# AudioControllerSchematic_Photoresistor.net
KiCad netlist of a schematic drawn in EAGLE
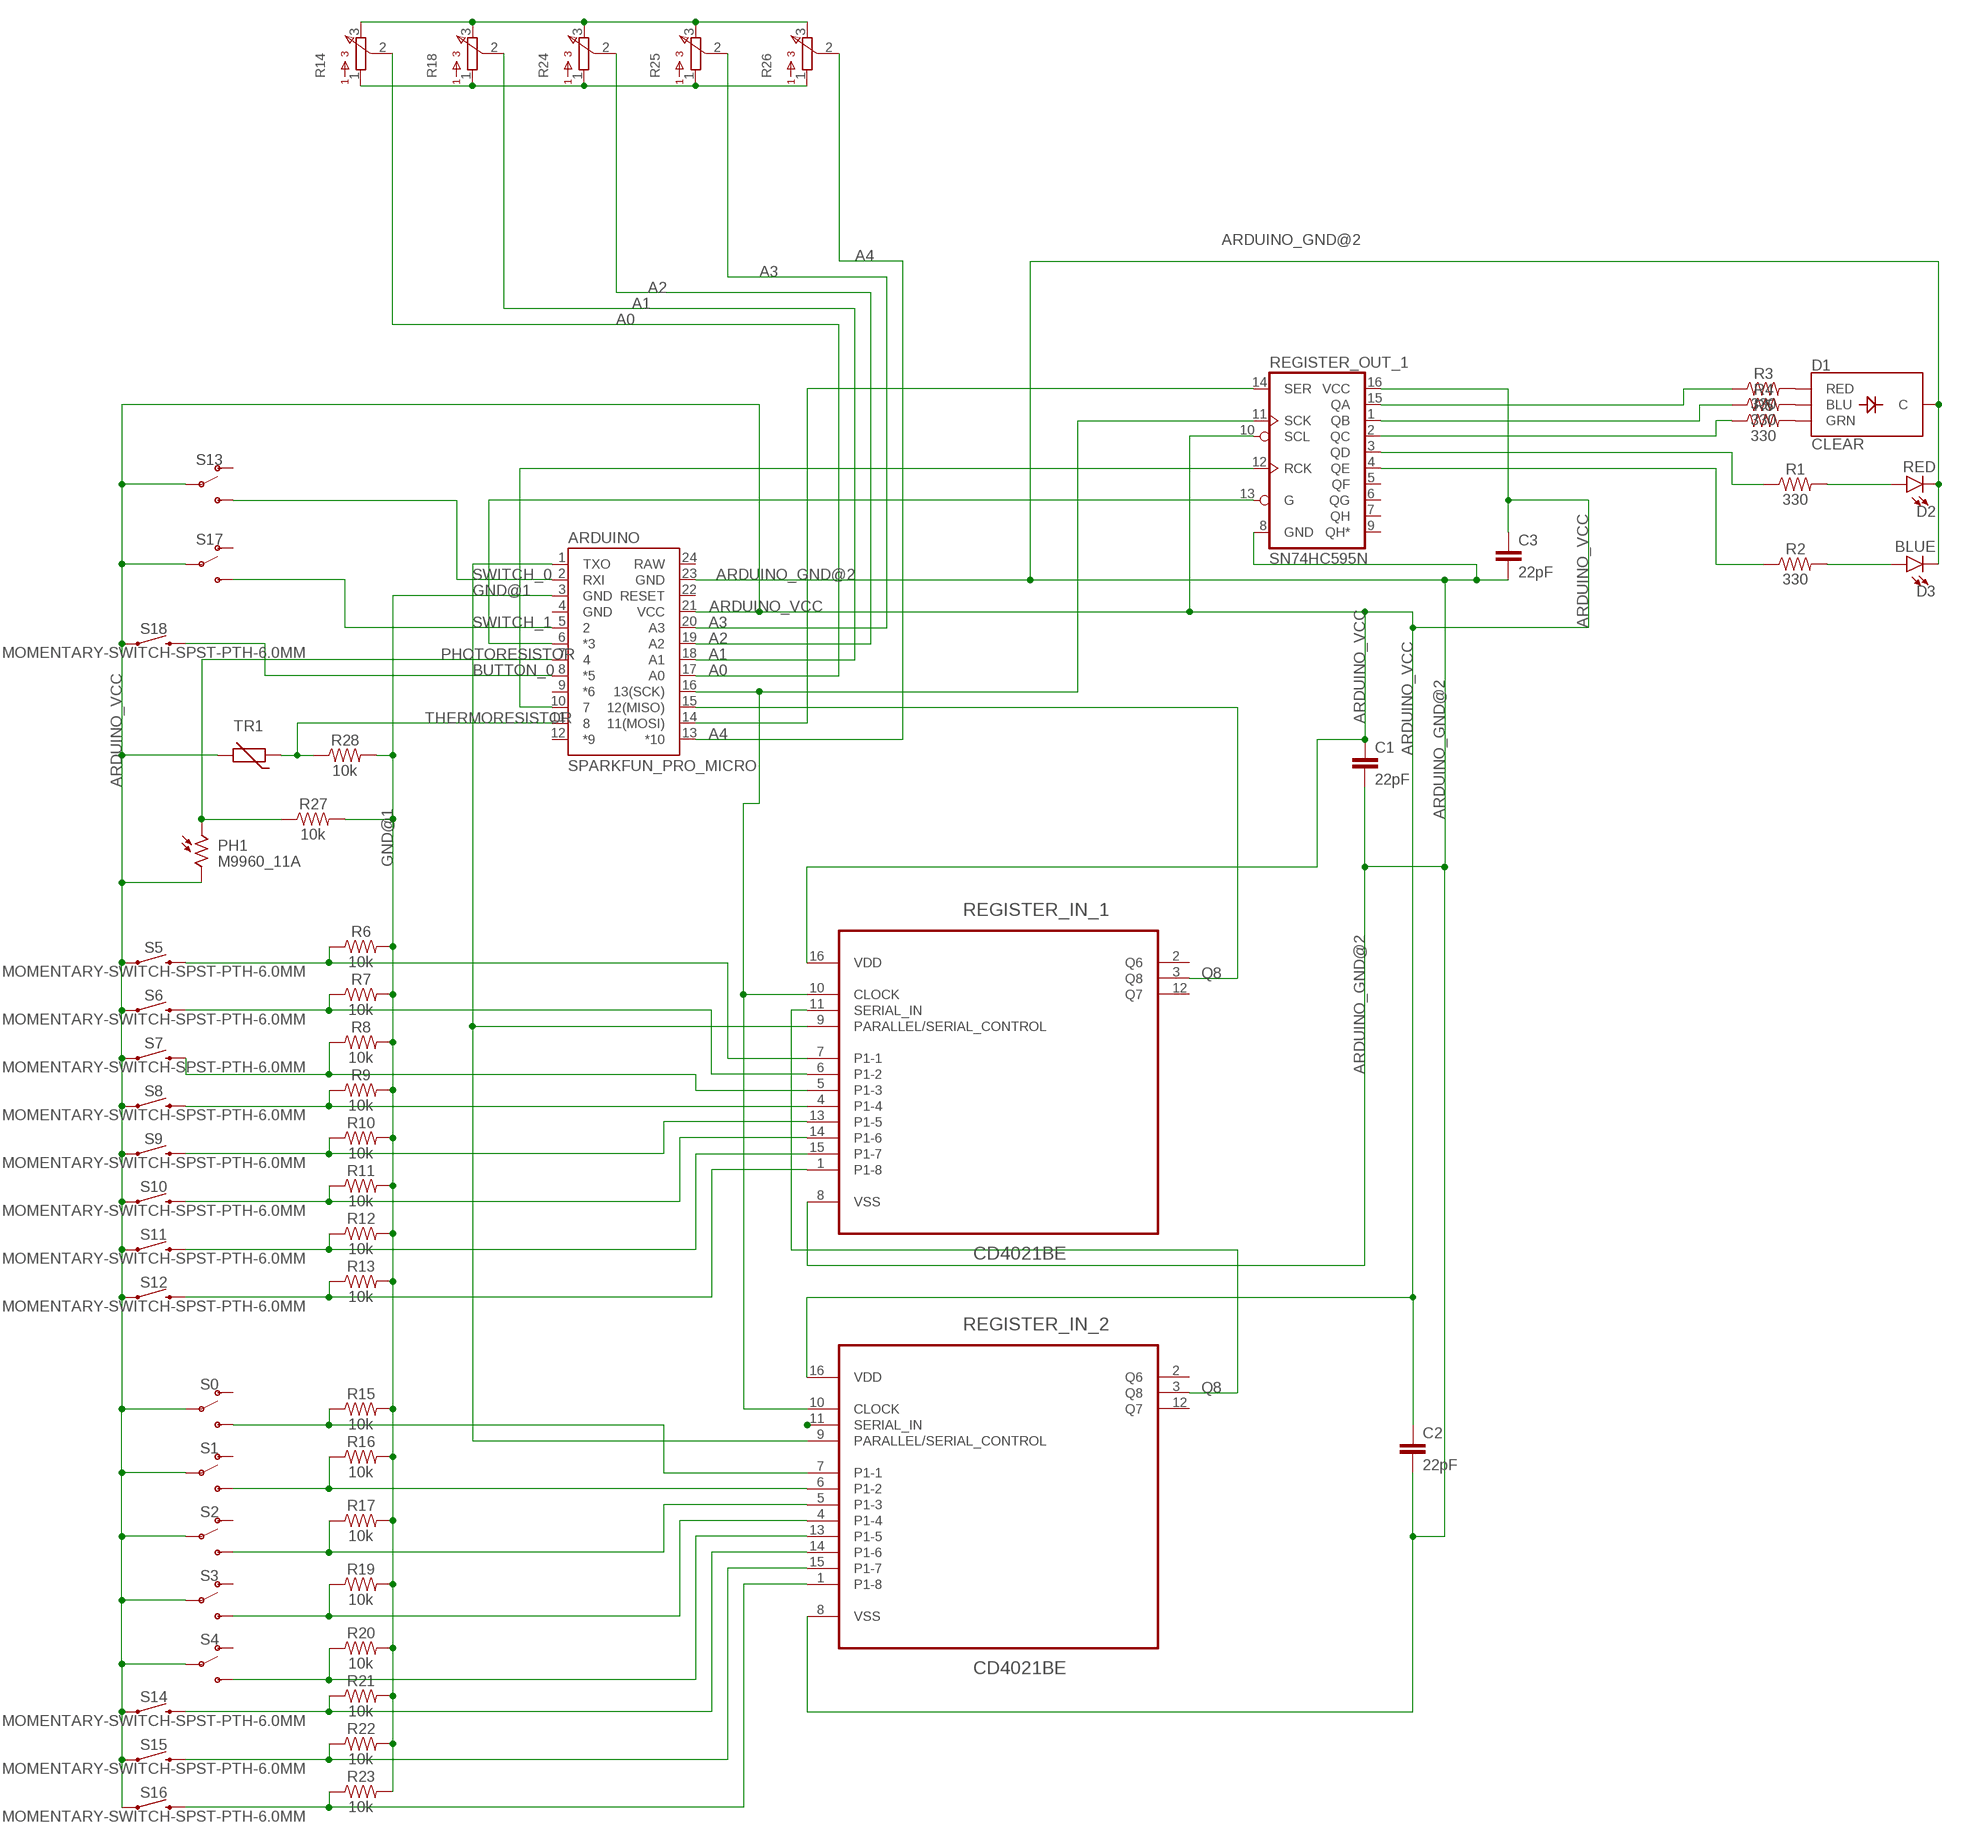
[diagram p0: schematic, sheet 1]

(export (version "E")
  (design (tool "Eeschema 10.0.6"))
  (components
    (comp (ref "ARDUINO")
      (value "SPARKFUN_PRO_MICRO")
      (footprint "eagle-import:SPARKFUN_PRO_MICRO")
      (libsource (lib "eagle-import") (part "SPARKFUN_PRO_MICRO"))
    )
    (comp (ref "C1")
      (value "22pF")
      (footprint "eagle-import:0603")
      (libsource (lib "eagle-import") (part "22PF-0603-50V-5%"))
    )
    (comp (ref "C2")
      (value "22pF")
      (footprint "eagle-import:0603")
      (libsource (lib "eagle-import") (part "22PF-0603-50V-5%"))
    )
    (comp (ref "C3")
      (value "22pF")
      (footprint "eagle-import:0603")
      (libsource (lib "eagle-import") (part "22PF-0603-50V-5%"))
    )
    (comp (ref "D1")
      (value "CLEAR")
      (footprint "eagle-import:LED-RGB-THRU")
      (libsource (lib "eagle-import") (part "LED-RGB-CCCLEAR"))
    )
    (comp (ref "D2")
      (value "RED")
      (footprint "eagle-import:LED-0603")
      (libsource (lib "eagle-import") (part "LED-RED0603"))
    )
    (comp (ref "D3")
      (value "BLUE")
      (footprint "eagle-import:LED-0603")
      (libsource (lib "eagle-import") (part "LED-BLUE0603"))
    )
    (comp (ref "PH1")
      (value "M9960_11A")
      (footprint "eagle-import:M9960")
      (libsource (lib "eagle-import") (part "M9960_11A"))
    )
    (comp (ref "R1")
      (value "330")
      (footprint "eagle-import:0603")
      (libsource (lib "eagle-import") (part "330OHM-0603-1/10W-1%"))
    )
    (comp (ref "R2")
      (value "330")
      (footprint "eagle-import:0603")
      (libsource (lib "eagle-import") (part "330OHM-0603-1/10W-1%"))
    )
    (comp (ref "R3")
      (value "330")
      (footprint "eagle-import:0603")
      (libsource (lib "eagle-import") (part "330OHM-0603-1/10W-1%"))
    )
    (comp (ref "R4")
      (value "330")
      (footprint "eagle-import:0603")
      (libsource (lib "eagle-import") (part "330OHM-0603-1/10W-1%"))
    )
    (comp (ref "R5")
      (value "330")
      (footprint "eagle-import:0603")
      (libsource (lib "eagle-import") (part "330OHM-0603-1/10W-1%"))
    )
    (comp (ref "R6")
      (value "10k")
      (footprint "eagle-import:0603")
      (libsource (lib "eagle-import") (part "10KOHM-0603-1/10W-1%"))
    )
    (comp (ref "R7")
      (value "10k")
      (footprint "eagle-import:0603")
      (libsource (lib "eagle-import") (part "10KOHM-0603-1/10W-1%"))
    )
    (comp (ref "R8")
      (value "10k")
      (footprint "eagle-import:0603")
      (libsource (lib "eagle-import") (part "10KOHM-0603-1/10W-1%"))
    )
    (comp (ref "R9")
      (value "10k")
      (footprint "eagle-import:0603")
      (libsource (lib "eagle-import") (part "10KOHM-0603-1/10W-1%"))
    )
    (comp (ref "R10")
      (value "10k")
      (footprint "eagle-import:0603")
      (libsource (lib "eagle-import") (part "10KOHM-0603-1/10W-1%"))
    )
    (comp (ref "R11")
      (value "10k")
      (footprint "eagle-import:0603")
      (libsource (lib "eagle-import") (part "10KOHM-0603-1/10W-1%"))
    )
    (comp (ref "R12")
      (value "10k")
      (footprint "eagle-import:0603")
      (libsource (lib "eagle-import") (part "10KOHM-0603-1/10W-1%"))
    )
    (comp (ref "R13")
      (value "10k")
      (footprint "eagle-import:0603")
      (libsource (lib "eagle-import") (part "10KOHM-0603-1/10W-1%"))
    )
    (comp (ref "R14") (value "91") (footprint "eagle-import:91") (libsource (lib "eagle-import") (part "91")))
    (comp (ref "R15")
      (value "10k")
      (footprint "eagle-import:0603")
      (libsource (lib "eagle-import") (part "10KOHM-0603-1/10W-1%"))
    )
    (comp (ref "R16")
      (value "10k")
      (footprint "eagle-import:0603")
      (libsource (lib "eagle-import") (part "10KOHM-0603-1/10W-1%"))
    )
    (comp (ref "R17")
      (value "10k")
      (footprint "eagle-import:0603")
      (libsource (lib "eagle-import") (part "10KOHM-0603-1/10W-1%"))
    )
    (comp (ref "R18") (value "91") (footprint "eagle-import:91") (libsource (lib "eagle-import") (part "91")))
    (comp (ref "R19")
      (value "10k")
      (footprint "eagle-import:0603")
      (libsource (lib "eagle-import") (part "10KOHM-0603-1/10W-1%"))
    )
    (comp (ref "R20")
      (value "10k")
      (footprint "eagle-import:0603")
      (libsource (lib "eagle-import") (part "10KOHM-0603-1/10W-1%"))
    )
    (comp (ref "R21")
      (value "10k")
      (footprint "eagle-import:0603")
      (libsource (lib "eagle-import") (part "10KOHM-0603-1/10W-1%"))
    )
    (comp (ref "R22")
      (value "10k")
      (footprint "eagle-import:0603")
      (libsource (lib "eagle-import") (part "10KOHM-0603-1/10W-1%"))
    )
    (comp (ref "R23")
      (value "10k")
      (footprint "eagle-import:0603")
      (libsource (lib "eagle-import") (part "10KOHM-0603-1/10W-1%"))
    )
    (comp (ref "R24") (value "91") (footprint "eagle-import:91") (libsource (lib "eagle-import") (part "91")))
    (comp (ref "R25") (value "91") (footprint "eagle-import:91") (libsource (lib "eagle-import") (part "91")))
    (comp (ref "R26") (value "91") (footprint "eagle-import:91") (libsource (lib "eagle-import") (part "91")))
    (comp (ref "R27")
      (value "10k")
      (footprint "eagle-import:0603")
      (libsource (lib "eagle-import") (part "10KOHM-0603-1/10W-1%"))
    )
    (comp (ref "R28")
      (value "10k")
      (footprint "eagle-import:0603")
      (libsource (lib "eagle-import") (part "10KOHM-0603-1/10W-1%"))
    )
    (comp (ref "REGISTER_IN_1")
      (value "CD4021BE")
      (footprint "eagle-import:DIP254P762X508-16")
      (fields (field (name "MF") "Texas"))
      (libsource (lib "eagle-import") (part "CD4021BE"))
    )
    (comp (ref "REGISTER_IN_2")
      (value "CD4021BE")
      (footprint "eagle-import:DIP254P762X508-16")
      (fields (field (name "MF") "Texas"))
      (libsource (lib "eagle-import") (part "CD4021BE"))
    )
    (comp (ref "REGISTER_OUT_1")
      (value "SN74HC595N")
      (footprint "eagle-import:DIP16")
      (libsource (lib "eagle-import") (part "74595NHC"))
    )
    (comp (ref "S0")
      (value "SWITCH-SPDT-PTH-11.6X4.0MM")
      (footprint "eagle-import:SWITCH_SPDT_PTH_11.6X4.0MM")
      (libsource (lib "eagle-import") (part "SWITCH-SPDT-PTH-11.6X4.0MM"))
    )
    (comp (ref "S1")
      (value "SWITCH-SPDT-PTH-11.6X4.0MM")
      (footprint "eagle-import:SWITCH_SPDT_PTH_11.6X4.0MM")
      (libsource (lib "eagle-import") (part "SWITCH-SPDT-PTH-11.6X4.0MM"))
    )
    (comp (ref "S2")
      (value "SWITCH-SPDT-PTH-11.6X4.0MM")
      (footprint "eagle-import:SWITCH_SPDT_PTH_11.6X4.0MM")
      (libsource (lib "eagle-import") (part "SWITCH-SPDT-PTH-11.6X4.0MM"))
    )
    (comp (ref "S3")
      (value "SWITCH-SPDT-PTH-11.6X4.0MM")
      (footprint "eagle-import:SWITCH_SPDT_PTH_11.6X4.0MM")
      (libsource (lib "eagle-import") (part "SWITCH-SPDT-PTH-11.6X4.0MM"))
    )
    (comp (ref "S4")
      (value "SWITCH-SPDT-PTH-11.6X4.0MM")
      (footprint "eagle-import:SWITCH_SPDT_PTH_11.6X4.0MM")
      (libsource (lib "eagle-import") (part "SWITCH-SPDT-PTH-11.6X4.0MM"))
    )
    (comp (ref "S5")
      (value "MOMENTARY-SWITCH-SPST-PTH-6.0MM")
      (footprint "eagle-import:TACTILE_SWITCH_PTH_6.0MM")
      (libsource (lib "eagle-import") (part "MOMENTARY-SWITCH-SPST-PTH-6.0MM"))
    )
    (comp (ref "S6")
      (value "MOMENTARY-SWITCH-SPST-PTH-6.0MM")
      (footprint "eagle-import:TACTILE_SWITCH_PTH_6.0MM")
      (libsource (lib "eagle-import") (part "MOMENTARY-SWITCH-SPST-PTH-6.0MM"))
    )
    (comp (ref "S7")
      (value "MOMENTARY-SWITCH-SPST-PTH-6.0MM")
      (footprint "eagle-import:TACTILE_SWITCH_PTH_6.0MM")
      (libsource (lib "eagle-import") (part "MOMENTARY-SWITCH-SPST-PTH-6.0MM"))
    )
    (comp (ref "S8")
      (value "MOMENTARY-SWITCH-SPST-PTH-6.0MM")
      (footprint "eagle-import:TACTILE_SWITCH_PTH_6.0MM")
      (libsource (lib "eagle-import") (part "MOMENTARY-SWITCH-SPST-PTH-6.0MM"))
    )
    (comp (ref "S9")
      (value "MOMENTARY-SWITCH-SPST-PTH-6.0MM")
      (footprint "eagle-import:TACTILE_SWITCH_PTH_6.0MM")
      (libsource (lib "eagle-import") (part "MOMENTARY-SWITCH-SPST-PTH-6.0MM"))
    )
    (comp (ref "S10")
      (value "MOMENTARY-SWITCH-SPST-PTH-6.0MM")
      (footprint "eagle-import:TACTILE_SWITCH_PTH_6.0MM")
      (libsource (lib "eagle-import") (part "MOMENTARY-SWITCH-SPST-PTH-6.0MM"))
    )
    (comp (ref "S11")
      (value "MOMENTARY-SWITCH-SPST-PTH-6.0MM")
      (footprint "eagle-import:TACTILE_SWITCH_PTH_6.0MM")
      (libsource (lib "eagle-import") (part "MOMENTARY-SWITCH-SPST-PTH-6.0MM"))
    )
    (comp (ref "S12")
      (value "MOMENTARY-SWITCH-SPST-PTH-6.0MM")
      (footprint "eagle-import:TACTILE_SWITCH_PTH_6.0MM")
      (libsource (lib "eagle-import") (part "MOMENTARY-SWITCH-SPST-PTH-6.0MM"))
    )
    (comp (ref "S13")
      (value "SWITCH-SPDT-PTH-11.6X4.0MM")
      (footprint "eagle-import:SWITCH_SPDT_PTH_11.6X4.0MM")
      (libsource (lib "eagle-import") (part "SWITCH-SPDT-PTH-11.6X4.0MM"))
    )
    (comp (ref "S14")
      (value "MOMENTARY-SWITCH-SPST-PTH-6.0MM")
      (footprint "eagle-import:TACTILE_SWITCH_PTH_6.0MM")
      (libsource (lib "eagle-import") (part "MOMENTARY-SWITCH-SPST-PTH-6.0MM"))
    )
    (comp (ref "S15")
      (value "MOMENTARY-SWITCH-SPST-PTH-6.0MM")
      (footprint "eagle-import:TACTILE_SWITCH_PTH_6.0MM")
      (libsource (lib "eagle-import") (part "MOMENTARY-SWITCH-SPST-PTH-6.0MM"))
    )
    (comp (ref "S16")
      (value "MOMENTARY-SWITCH-SPST-PTH-6.0MM")
      (footprint "eagle-import:TACTILE_SWITCH_PTH_6.0MM")
      (libsource (lib "eagle-import") (part "MOMENTARY-SWITCH-SPST-PTH-6.0MM"))
    )
    (comp (ref "S17")
      (value "SWITCH-SPDT-PTH-11.6X4.0MM")
      (footprint "eagle-import:SWITCH_SPDT_PTH_11.6X4.0MM")
      (libsource (lib "eagle-import") (part "SWITCH-SPDT-PTH-11.6X4.0MM"))
    )
    (comp (ref "S18")
      (value "MOMENTARY-SWITCH-SPST-PTH-6.0MM")
      (footprint "eagle-import:TACTILE_SWITCH_PTH_6.0MM")
      (libsource (lib "eagle-import") (part "MOMENTARY-SWITCH-SPST-PTH-6.0MM"))
    )
    (comp (ref "TR1")
      (value "THERMISTOR_R-2,5")
      (footprint "eagle-import:RS-2,5")
      (libsource (lib "eagle-import") (part "THERMISTOR_R-2,5"))
    )
  )
  (nets
    (net (code "1") (name "/A0") (class "Default")
      (node (ref "ARDUINO") (pin "17") (pinfunction "A0_17") (pintype "bidirectional"))
      (node (ref "R14") (pin "2") (pinfunction "2_2") (pintype "passive"))
    )
    (net (code "2") (name "/A1") (class "Default")
      (node (ref "ARDUINO") (pin "18") (pinfunction "A1_18") (pintype "bidirectional"))
      (node (ref "R18") (pin "2") (pinfunction "2_2") (pintype "passive"))
    )
    (net (code "3") (name "/A2") (class "Default")
      (node (ref "ARDUINO") (pin "19") (pinfunction "A2_19") (pintype "bidirectional"))
      (node (ref "R24") (pin "2") (pinfunction "2_2") (pintype "passive"))
    )
    (net (code "4") (name "/A3") (class "Default")
      (node (ref "ARDUINO") (pin "20") (pinfunction "A3_20") (pintype "bidirectional"))
      (node (ref "R25") (pin "2") (pinfunction "2_2") (pintype "passive"))
    )
    (net (code "5") (name "/A4") (class "Default")
      (node (ref "ARDUINO") (pin "13") (pinfunction "*10_13") (pintype "bidirectional"))
      (node (ref "R26") (pin "2") (pinfunction "2_2") (pintype "passive"))
    )
    (net (code "6") (name "/ARDUINO_GND@2") (class "Default")
      (node (ref "ARDUINO") (pin "23") (pinfunction "GND_23") (pintype "power_in"))
      (node (ref "C1") (pin "2") (pinfunction "2_2") (pintype "passive"))
      (node (ref "C2") (pin "2") (pinfunction "2_2") (pintype "passive"))
      (node (ref "C3") (pin "2") (pinfunction "2_2") (pintype "passive"))
      (node (ref "D1") (pin "2") (pinfunction "C_2") (pintype "bidirectional"))
      (node (ref "D2") (pin "C") (pinfunction "C_C") (pintype "passive"))
      (node (ref "D3") (pin "C") (pinfunction "C_C") (pintype "passive"))
      (node (ref "REGISTER_IN_1") (pin "8") (pinfunction "VSS_8") (pintype "passive"))
      (node (ref "REGISTER_IN_2") (pin "8") (pinfunction "VSS_8") (pintype "passive"))
      (node (ref "REGISTER_OUT_1") (pin "8") (pinfunction "GND_8") (pintype "power_in"))
    )
    (net (code "7") (name "/ARDUINO_VCC") (class "Default")
      (node (ref "ARDUINO") (pin "21") (pinfunction "VCC_21") (pintype "power_in"))
      (node (ref "C1") (pin "1") (pinfunction "1_1") (pintype "passive"))
      (node (ref "C2") (pin "1") (pinfunction "1_1") (pintype "passive"))
      (node (ref "C3") (pin "1") (pinfunction "1_1") (pintype "passive"))
      (node (ref "PH1") (pin "2") (pinfunction "2_2") (pintype "passive"))
      (node (ref "REGISTER_IN_1") (pin "16") (pinfunction "VDD_16") (pintype "power_in"))
      (node (ref "REGISTER_IN_2") (pin "16") (pinfunction "VDD_16") (pintype "power_in"))
      (node (ref "REGISTER_OUT_1") (pin "10") (pinfunction "SCL_10") (pintype "input"))
      (node (ref "REGISTER_OUT_1") (pin "16") (pinfunction "VCC_16") (pintype "power_in"))
      (node (ref "S0") (pin "2") (pinfunction "P_2") (pintype "passive"))
      (node (ref "S1") (pin "2") (pinfunction "P_2") (pintype "passive"))
      (node (ref "S10") (pin "1") (pinfunction "1_1") (pintype "passive"))
      (node (ref "S11") (pin "1") (pinfunction "1_1") (pintype "passive"))
      (node (ref "S12") (pin "1") (pinfunction "1_1") (pintype "passive"))
      (node (ref "S13") (pin "2") (pinfunction "P_2") (pintype "passive"))
      (node (ref "S14") (pin "1") (pinfunction "1_1") (pintype "passive"))
      (node (ref "S15") (pin "1") (pinfunction "1_1") (pintype "passive"))
      (node (ref "S16") (pin "1") (pinfunction "1_1") (pintype "passive"))
      (node (ref "S17") (pin "2") (pinfunction "P_2") (pintype "passive"))
      (node (ref "S18") (pin "1") (pinfunction "1_1") (pintype "passive"))
      (node (ref "S2") (pin "2") (pinfunction "P_2") (pintype "passive"))
      (node (ref "S3") (pin "2") (pinfunction "P_2") (pintype "passive"))
      (node (ref "S4") (pin "2") (pinfunction "P_2") (pintype "passive"))
      (node (ref "S5") (pin "1") (pinfunction "1_1") (pintype "passive"))
      (node (ref "S6") (pin "1") (pinfunction "1_1") (pintype "passive"))
      (node (ref "S7") (pin "1") (pinfunction "1_1") (pintype "passive"))
      (node (ref "S8") (pin "1") (pinfunction "1_1") (pintype "passive"))
      (node (ref "S9") (pin "1") (pinfunction "1_1") (pintype "passive"))
      (node (ref "TR1") (pin "2") (pinfunction "2_2") (pintype "passive"))
    )
    (net (code "8") (name "/BUTTON_0") (class "Default")
      (node (ref "ARDUINO") (pin "8") (pinfunction "*5_8") (pintype "bidirectional"))
      (node (ref "S18") (pin "3") (pinfunction "2_3") (pintype "passive"))
    )
    (net (code "9") (name "/GND") (class "Default")
      (node (ref "ARDUINO") (pin "4") (pinfunction "GND_4") (pintype "power_in"))
    )
    (net (code "10") (name "/GND@1") (class "Default")
      (node (ref "ARDUINO") (pin "3") (pinfunction "GND_3") (pintype "power_in"))
      (node (ref "R10") (pin "2") (pinfunction "2_2") (pintype "passive"))
      (node (ref "R11") (pin "2") (pinfunction "2_2") (pintype "passive"))
      (node (ref "R12") (pin "2") (pinfunction "2_2") (pintype "passive"))
      (node (ref "R13") (pin "2") (pinfunction "2_2") (pintype "passive"))
      (node (ref "R15") (pin "2") (pinfunction "2_2") (pintype "passive"))
      (node (ref "R16") (pin "2") (pinfunction "2_2") (pintype "passive"))
      (node (ref "R17") (pin "2") (pinfunction "2_2") (pintype "passive"))
      (node (ref "R19") (pin "2") (pinfunction "2_2") (pintype "passive"))
      (node (ref "R20") (pin "2") (pinfunction "2_2") (pintype "passive"))
      (node (ref "R21") (pin "2") (pinfunction "2_2") (pintype "passive"))
      (node (ref "R22") (pin "2") (pinfunction "2_2") (pintype "passive"))
      (node (ref "R23") (pin "2") (pinfunction "2_2") (pintype "passive"))
      (node (ref "R27") (pin "2") (pinfunction "2_2") (pintype "passive"))
      (node (ref "R28") (pin "2") (pinfunction "2_2") (pintype "passive"))
      (node (ref "R6") (pin "2") (pinfunction "2_2") (pintype "passive"))
      (node (ref "R7") (pin "2") (pinfunction "2_2") (pintype "passive"))
      (node (ref "R8") (pin "2") (pinfunction "2_2") (pintype "passive"))
      (node (ref "R9") (pin "2") (pinfunction "2_2") (pintype "passive"))
    )
    (net (code "11") (name "/PHOTORESISTOR") (class "Default")
      (node (ref "ARDUINO") (pin "7") (pinfunction "4_7") (pintype "bidirectional"))
      (node (ref "PH1") (pin "1") (pinfunction "1_1") (pintype "passive"))
      (node (ref "R27") (pin "1") (pinfunction "1_1") (pintype "passive"))
    )
    (net (code "12") (name "/Q8") (class "Default")
      (node (ref "ARDUINO") (pin "15") (pinfunction "12(MISO)_15") (pintype "bidirectional"))
      (node (ref "REGISTER_IN_1") (pin "11") (pinfunction "SERIAL_IN_11") (pintype "input"))
      (node (ref "REGISTER_IN_1") (pin "3") (pinfunction "Q8_3") (pintype "output"))
      (node (ref "REGISTER_IN_2") (pin "3") (pinfunction "Q8_3") (pintype "output"))
    )
    (net (code "13") (name "/RAW") (class "Default")
      (node (ref "ARDUINO") (pin "24") (pinfunction "RAW_24") (pintype "power_in"))
    )
    (net (code "14") (name "/SWITCH_0") (class "Default")
      (node (ref "ARDUINO") (pin "2") (pinfunction "RXI_2") (pintype "bidirectional"))
      (node (ref "S13") (pin "3") (pinfunction "S_3") (pintype "passive"))
    )
    (net (code "15") (name "/SWITCH_1") (class "Default")
      (node (ref "ARDUINO") (pin "5") (pinfunction "2_5") (pintype "bidirectional"))
      (node (ref "S17") (pin "3") (pinfunction "S_3") (pintype "passive"))
    )
    (net (code "16") (name "/THERMORESISTOR") (class "Default")
      (node (ref "ARDUINO") (pin "11") (pinfunction "8_11") (pintype "bidirectional"))
      (node (ref "R28") (pin "1") (pinfunction "1_1") (pintype "passive"))
      (node (ref "TR1") (pin "1") (pinfunction "1_1") (pintype "passive"))
    )
    (net (code "17") (name "Net-(ARDUINO-*3)") (class "Default")
      (node (ref "ARDUINO") (pin "6") (pinfunction "*3_6") (pintype "bidirectional"))
      (node (ref "REGISTER_OUT_1") (pin "13") (pinfunction "G_13") (pintype "input"))
    )
    (net (code "18") (name "Net-(ARDUINO-7)") (class "Default")
      (node (ref "ARDUINO") (pin "10") (pinfunction "7_10") (pintype "bidirectional"))
      (node (ref "REGISTER_OUT_1") (pin "12") (pinfunction "RCK_12") (pintype "input"))
    )
    (net (code "19") (name "Net-(ARDUINO-11(MOSI))") (class "Default")
      (node (ref "ARDUINO") (pin "14") (pinfunction "11(MOSI)_14") (pintype "bidirectional"))
      (node (ref "REGISTER_OUT_1") (pin "14") (pinfunction "SER_14") (pintype "input"))
    )
    (net (code "20") (name "Net-(ARDUINO-13(SCK))") (class "Default")
      (node (ref "ARDUINO") (pin "16") (pinfunction "13(SCK)_16") (pintype "bidirectional"))
      (node (ref "REGISTER_IN_1") (pin "10") (pinfunction "CLOCK_10") (pintype "input"))
      (node (ref "REGISTER_IN_2") (pin "10") (pinfunction "CLOCK_10") (pintype "input"))
      (node (ref "REGISTER_OUT_1") (pin "11") (pinfunction "SCK_11") (pintype "input"))
    )
    (net (code "21") (name "Net-(ARDUINO-TXO)") (class "Default")
      (node (ref "ARDUINO") (pin "1") (pinfunction "TXO_1") (pintype "bidirectional"))
      (node (ref "REGISTER_IN_1") (pin "9") (pinfunction "PARALLEL/SERIAL_CONTROL_9") (pintype "input"))
      (node (ref "REGISTER_IN_2") (pin "9") (pinfunction "PARALLEL/SERIAL_CONTROL_9") (pintype "input"))
    )
    (net (code "22") (name "Net-(D1-BLU)") (class "Default")
      (node (ref "D1") (pin "4") (pinfunction "BLU_4") (pintype "bidirectional"))
      (node (ref "R4") (pin "2") (pinfunction "2_2") (pintype "passive"))
    )
    (net (code "23") (name "Net-(D1-GRN)") (class "Default")
      (node (ref "D1") (pin "3") (pinfunction "GRN_3") (pintype "bidirectional"))
      (node (ref "R5") (pin "2") (pinfunction "2_2") (pintype "passive"))
    )
    (net (code "24") (name "Net-(D1-RED)") (class "Default")
      (node (ref "D1") (pin "1") (pinfunction "RED_1") (pintype "bidirectional"))
      (node (ref "R3") (pin "2") (pinfunction "2_2") (pintype "passive"))
    )
    (net (code "25") (name "Net-(D2-PadA)") (class "Default")
      (node (ref "D2") (pin "A") (pinfunction "A_A") (pintype "passive"))
      (node (ref "R1") (pin "2") (pinfunction "2_2") (pintype "passive"))
    )
    (net (code "26") (name "Net-(D3-PadA)") (class "Default")
      (node (ref "D3") (pin "A") (pinfunction "A_A") (pintype "passive"))
      (node (ref "R2") (pin "2") (pinfunction "2_2") (pintype "passive"))
    )
    (net (code "27") (name "Net-(R14-Pad1)") (class "Default")
      (node (ref "R14") (pin "1") (pinfunction "1_1") (pintype "passive"))
      (node (ref "R18") (pin "1") (pinfunction "1_1") (pintype "passive"))
      (node (ref "R24") (pin "1") (pinfunction "1_1") (pintype "passive"))
      (node (ref "R25") (pin "1") (pinfunction "1_1") (pintype "passive"))
      (node (ref "R26") (pin "1") (pinfunction "1_1") (pintype "passive"))
    )
    (net (code "28") (name "Net-(R14-Pad3)") (class "Default")
      (node (ref "R14") (pin "3") (pinfunction "3_3") (pintype "passive"))
      (node (ref "R18") (pin "3") (pinfunction "3_3") (pintype "passive"))
      (node (ref "R24") (pin "3") (pinfunction "3_3") (pintype "passive"))
      (node (ref "R25") (pin "3") (pinfunction "3_3") (pintype "passive"))
      (node (ref "R26") (pin "3") (pinfunction "3_3") (pintype "passive"))
    )
    (net (code "29") (name "Net-(REGISTER_IN_1-P1-1)") (class "Default")
      (node (ref "R6") (pin "1") (pinfunction "1_1") (pintype "passive"))
      (node (ref "REGISTER_IN_1") (pin "7") (pinfunction "P1-1_7") (pintype "input"))
      (node (ref "S5") (pin "3") (pinfunction "2_3") (pintype "passive"))
    )
    (net (code "30") (name "Net-(REGISTER_IN_1-P1-2)") (class "Default")
      (node (ref "R7") (pin "1") (pinfunction "1_1") (pintype "passive"))
      (node (ref "REGISTER_IN_1") (pin "6") (pinfunction "P1-2_6") (pintype "input"))
      (node (ref "S6") (pin "3") (pinfunction "2_3") (pintype "passive"))
    )
    (net (code "31") (name "Net-(REGISTER_IN_1-P1-3)") (class "Default")
      (node (ref "R8") (pin "1") (pinfunction "1_1") (pintype "passive"))
      (node (ref "REGISTER_IN_1") (pin "5") (pinfunction "P1-3_5") (pintype "input"))
      (node (ref "S7") (pin "3") (pinfunction "2_3") (pintype "passive"))
    )
    (net (code "32") (name "Net-(REGISTER_IN_1-P1-4)") (class "Default")
      (node (ref "R9") (pin "1") (pinfunction "1_1") (pintype "passive"))
      (node (ref "REGISTER_IN_1") (pin "4") (pinfunction "P1-4_4") (pintype "input"))
      (node (ref "S8") (pin "3") (pinfunction "2_3") (pintype "passive"))
    )
    (net (code "33") (name "Net-(REGISTER_IN_1-P1-5)") (class "Default")
      (node (ref "R10") (pin "1") (pinfunction "1_1") (pintype "passive"))
      (node (ref "REGISTER_IN_1") (pin "13") (pinfunction "P1-5_13") (pintype "input"))
      (node (ref "S9") (pin "3") (pinfunction "2_3") (pintype "passive"))
    )
    (net (code "34") (name "Net-(REGISTER_IN_1-P1-6)") (class "Default")
      (node (ref "R11") (pin "1") (pinfunction "1_1") (pintype "passive"))
      (node (ref "REGISTER_IN_1") (pin "14") (pinfunction "P1-6_14") (pintype "input"))
      (node (ref "S10") (pin "3") (pinfunction "2_3") (pintype "passive"))
    )
    (net (code "35") (name "Net-(REGISTER_IN_1-P1-7)") (class "Default")
      (node (ref "R12") (pin "1") (pinfunction "1_1") (pintype "passive"))
      (node (ref "REGISTER_IN_1") (pin "15") (pinfunction "P1-7_15") (pintype "input"))
      (node (ref "S11") (pin "3") (pinfunction "2_3") (pintype "passive"))
    )
    (net (code "36") (name "Net-(REGISTER_IN_1-P1-8)") (class "Default")
      (node (ref "R13") (pin "1") (pinfunction "1_1") (pintype "passive"))
      (node (ref "REGISTER_IN_1") (pin "1") (pinfunction "P1-8_1") (pintype "input"))
      (node (ref "S12") (pin "3") (pinfunction "2_3") (pintype "passive"))
    )
    (net (code "37") (name "Net-(REGISTER_IN_2-P1-1)") (class "Default")
      (node (ref "R15") (pin "1") (pinfunction "1_1") (pintype "passive"))
      (node (ref "REGISTER_IN_2") (pin "7") (pinfunction "P1-1_7") (pintype "input"))
      (node (ref "S0") (pin "3") (pinfunction "S_3") (pintype "passive"))
    )
    (net (code "38") (name "Net-(REGISTER_IN_2-P1-2)") (class "Default")
      (node (ref "R16") (pin "1") (pinfunction "1_1") (pintype "passive"))
      (node (ref "REGISTER_IN_2") (pin "6") (pinfunction "P1-2_6") (pintype "input"))
      (node (ref "S1") (pin "3") (pinfunction "S_3") (pintype "passive"))
    )
    (net (code "39") (name "Net-(REGISTER_IN_2-P1-3)") (class "Default")
      (node (ref "R17") (pin "1") (pinfunction "1_1") (pintype "passive"))
      (node (ref "REGISTER_IN_2") (pin "5") (pinfunction "P1-3_5") (pintype "input"))
      (node (ref "S2") (pin "3") (pinfunction "S_3") (pintype "passive"))
    )
    (net (code "40") (name "Net-(REGISTER_IN_2-P1-4)") (class "Default")
      (node (ref "R19") (pin "1") (pinfunction "1_1") (pintype "passive"))
      (node (ref "REGISTER_IN_2") (pin "4") (pinfunction "P1-4_4") (pintype "input"))
      (node (ref "S3") (pin "3") (pinfunction "S_3") (pintype "passive"))
    )
    (net (code "41") (name "Net-(REGISTER_IN_2-P1-5)") (class "Default")
      (node (ref "R20") (pin "1") (pinfunction "1_1") (pintype "passive"))
      (node (ref "REGISTER_IN_2") (pin "13") (pinfunction "P1-5_13") (pintype "input"))
      (node (ref "S4") (pin "3") (pinfunction "S_3") (pintype "passive"))
    )
    (net (code "42") (name "Net-(REGISTER_IN_2-P1-6)") (class "Default")
      (node (ref "R21") (pin "1") (pinfunction "1_1") (pintype "passive"))
      (node (ref "REGISTER_IN_2") (pin "14") (pinfunction "P1-6_14") (pintype "input"))
      (node (ref "S14") (pin "3") (pinfunction "2_3") (pintype "passive"))
    )
    (net (code "43") (name "Net-(REGISTER_IN_2-P1-7)") (class "Default")
      (node (ref "R22") (pin "1") (pinfunction "1_1") (pintype "passive"))
      (node (ref "REGISTER_IN_2") (pin "15") (pinfunction "P1-7_15") (pintype "input"))
      (node (ref "S15") (pin "3") (pinfunction "2_3") (pintype "passive"))
    )
    (net (code "44") (name "Net-(REGISTER_IN_2-P1-8)") (class "Default")
      (node (ref "R23") (pin "1") (pinfunction "1_1") (pintype "passive"))
      (node (ref "REGISTER_IN_2") (pin "1") (pinfunction "P1-8_1") (pintype "input"))
      (node (ref "S16") (pin "3") (pinfunction "2_3") (pintype "passive"))
    )
    (net (code "45") (name "Net-(REGISTER_OUT_1-QA)") (class "Default")
      (node (ref "R3") (pin "1") (pinfunction "1_1") (pintype "passive"))
      (node (ref "REGISTER_OUT_1") (pin "15") (pinfunction "QA_15") (pintype "tri_state"))
    )
    (net (code "46") (name "Net-(REGISTER_OUT_1-QB)") (class "Default")
      (node (ref "R4") (pin "1") (pinfunction "1_1") (pintype "passive"))
      (node (ref "REGISTER_OUT_1") (pin "1") (pinfunction "QB_1") (pintype "tri_state"))
    )
    (net (code "47") (name "Net-(REGISTER_OUT_1-QC)") (class "Default")
      (node (ref "R5") (pin "1") (pinfunction "1_1") (pintype "passive"))
      (node (ref "REGISTER_OUT_1") (pin "2") (pinfunction "QC_2") (pintype "tri_state"))
    )
    (net (code "48") (name "Net-(REGISTER_OUT_1-QD)") (class "Default")
      (node (ref "R1") (pin "1") (pinfunction "1_1") (pintype "passive"))
      (node (ref "REGISTER_OUT_1") (pin "3") (pinfunction "QD_3") (pintype "tri_state"))
    )
    (net (code "49") (name "Net-(REGISTER_OUT_1-QE)") (class "Default")
      (node (ref "R2") (pin "1") (pinfunction "1_1") (pintype "passive"))
      (node (ref "REGISTER_OUT_1") (pin "4") (pinfunction "QE_4") (pintype "tri_state"))
    )
    (net (code "50") (name "unconnected-(ARDUINO-*6-Pad9)") (class "Default")
      (node (ref "ARDUINO") (pin "9") (pinfunction "*6_9") (pintype "bidirectional"))
    )
    (net (code "51") (name "unconnected-(ARDUINO-*9-Pad12)") (class "Default")
      (node (ref "ARDUINO") (pin "12") (pinfunction "*9_12") (pintype "bidirectional"))
    )
    (net (code "52") (name "unconnected-(ARDUINO-RESET-Pad22)") (class "Default")
      (node (ref "ARDUINO") (pin "22") (pinfunction "RESET_22") (pintype "bidirectional"))
    )
    (net (code "53") (name "unconnected-(REGISTER_IN_1-Q6-Pad2)") (class "Default")
      (node (ref "REGISTER_IN_1") (pin "2") (pinfunction "Q6_2") (pintype "output"))
    )
    (net (code "54") (name "unconnected-(REGISTER_IN_1-Q7-Pad12)") (class "Default")
      (node (ref "REGISTER_IN_1") (pin "12") (pinfunction "Q7_12") (pintype "output"))
    )
    (net (code "55") (name "unconnected-(REGISTER_IN_2-Q6-Pad2)") (class "Default")
      (node (ref "REGISTER_IN_2") (pin "2") (pinfunction "Q6_2") (pintype "output"))
    )
    (net (code "56") (name "unconnected-(REGISTER_IN_2-Q7-Pad12)") (class "Default")
      (node (ref "REGISTER_IN_2") (pin "12") (pinfunction "Q7_12") (pintype "output"))
    )
    (net (code "57") (name "unconnected-(REGISTER_IN_2-SERIAL_IN-Pad11)") (class "Default")
      (node (ref "REGISTER_IN_2") (pin "11") (pinfunction "SERIAL_IN_11") (pintype "input"))
    )
    (net (code "58") (name "unconnected-(REGISTER_OUT_1-QF-Pad5)") (class "Default")
      (node (ref "REGISTER_OUT_1") (pin "5") (pinfunction "QF_5") (pintype "tri_state"))
    )
    (net (code "59") (name "unconnected-(REGISTER_OUT_1-QG-Pad6)") (class "Default")
      (node (ref "REGISTER_OUT_1") (pin "6") (pinfunction "QG_6") (pintype "tri_state"))
    )
    (net (code "60") (name "unconnected-(REGISTER_OUT_1-QH*-Pad9)") (class "Default")
      (node (ref "REGISTER_OUT_1") (pin "9") (pinfunction "QH*_9") (pintype "tri_state"))
    )
    (net (code "61") (name "unconnected-(REGISTER_OUT_1-QH-Pad7)") (class "Default")
      (node (ref "REGISTER_OUT_1") (pin "7") (pinfunction "QH_7") (pintype "tri_state"))
    )
    (net (code "62") (name "unconnected-(S0-O-Pad1)") (class "Default")
      (node (ref "S0") (pin "1") (pinfunction "O_1") (pintype "passive"))
    )
    (net (code "63") (name "unconnected-(S1-O-Pad1)") (class "Default")
      (node (ref "S1") (pin "1") (pinfunction "O_1") (pintype "passive"))
    )
    (net (code "64") (name "unconnected-(S2-O-Pad1)") (class "Default")
      (node (ref "S2") (pin "1") (pinfunction "O_1") (pintype "passive"))
    )
    (net (code "65") (name "unconnected-(S3-O-Pad1)") (class "Default")
      (node (ref "S3") (pin "1") (pinfunction "O_1") (pintype "passive"))
    )
    (net (code "66") (name "unconnected-(S4-O-Pad1)") (class "Default")
      (node (ref "S4") (pin "1") (pinfunction "O_1") (pintype "passive"))
    )
    (net (code "67") (name "unconnected-(S13-O-Pad1)") (class "Default")
      (node (ref "S13") (pin "1") (pinfunction "O_1") (pintype "passive"))
    )
    (net (code "68") (name "unconnected-(S17-O-Pad1)") (class "Default")
      (node (ref "S17") (pin "1") (pinfunction "O_1") (pintype "passive"))
    )
  )
)
